# top.net
KiCad netlist of a schematic drawn in Altium Designer
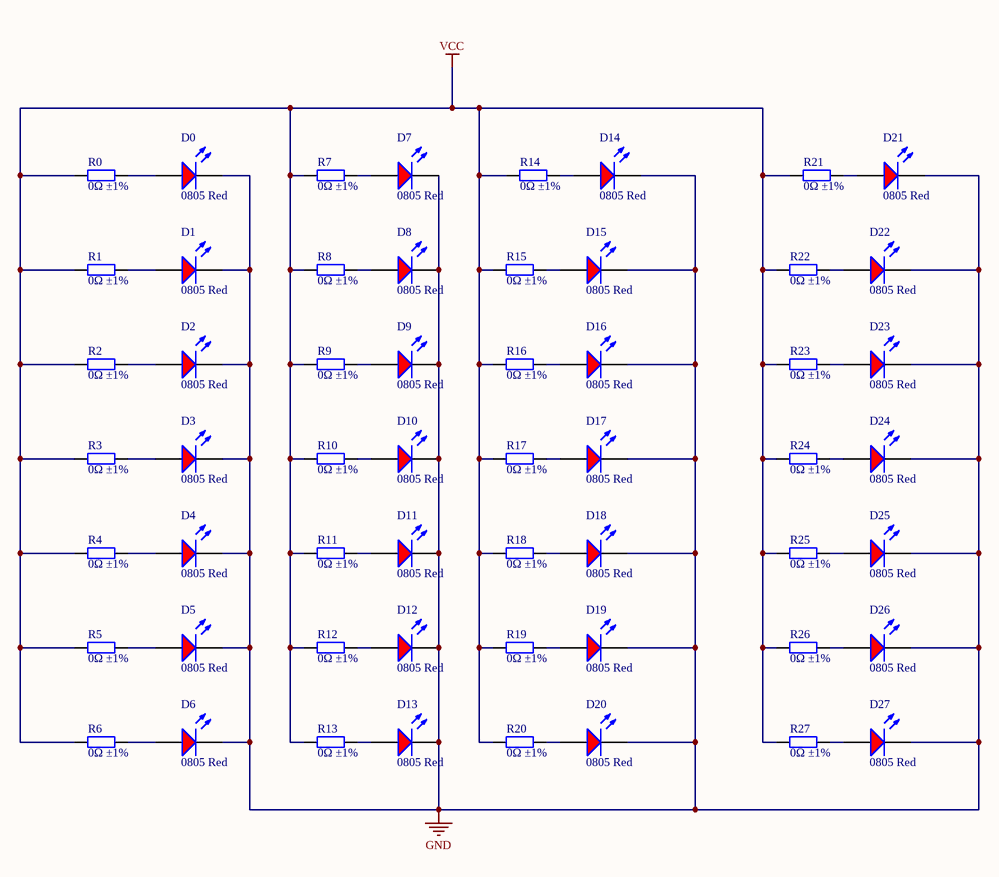
[diagram p0: top.SchDoc]

(export (version "E")
  (design (tool "Eeschema 10.0.6"))
  (components
    (comp (ref "D0")
      (value "0805 Red")
      (footprint "0805_LED_S1")
      (description "LED")
      (libsource (lib "Miscellaneous Devices LC") (part "0805 LED Red"))
    )
    (comp (ref "D1")
      (value "0805 Red")
      (footprint "0805_LED_S1")
      (description "LED")
      (libsource (lib "Miscellaneous Devices LC") (part "0805 LED Red"))
    )
    (comp (ref "D2")
      (value "0805 Red")
      (footprint "0805_LED_S1")
      (description "LED")
      (libsource (lib "Miscellaneous Devices LC") (part "0805 LED Red"))
    )
    (comp (ref "D3")
      (value "0805 Red")
      (footprint "0805_LED_S1")
      (description "LED")
      (libsource (lib "Miscellaneous Devices LC") (part "0805 LED Red"))
    )
    (comp (ref "D4")
      (value "0805 Red")
      (footprint "0805_LED_S1")
      (description "LED")
      (libsource (lib "Miscellaneous Devices LC") (part "0805 LED Red"))
    )
    (comp (ref "D5")
      (value "0805 Red")
      (footprint "0805_LED_S1")
      (description "LED")
      (libsource (lib "Miscellaneous Devices LC") (part "0805 LED Red"))
    )
    (comp (ref "D6")
      (value "0805 Red")
      (footprint "0805_LED_S1")
      (description "LED")
      (libsource (lib "Miscellaneous Devices LC") (part "0805 LED Red"))
    )
    (comp (ref "D7")
      (value "0805 Red")
      (footprint "0805_LED_S1")
      (description "LED")
      (libsource (lib "Miscellaneous Devices LC") (part "0805 LED Red"))
    )
    (comp (ref "D8")
      (value "0805 Red")
      (footprint "0805_LED_S1")
      (description "LED")
      (libsource (lib "Miscellaneous Devices LC") (part "0805 LED Red"))
    )
    (comp (ref "D9")
      (value "0805 Red")
      (footprint "0805_LED_S1")
      (description "LED")
      (libsource (lib "Miscellaneous Devices LC") (part "0805 LED Red"))
    )
    (comp (ref "D10")
      (value "0805 Red")
      (footprint "0805_LED_S1")
      (description "LED")
      (libsource (lib "Miscellaneous Devices LC") (part "0805 LED Red"))
    )
    (comp (ref "D11")
      (value "0805 Red")
      (footprint "0805_LED_S1")
      (description "LED")
      (libsource (lib "Miscellaneous Devices LC") (part "0805 LED Red"))
    )
    (comp (ref "D12")
      (value "0805 Red")
      (footprint "0805_LED_S1")
      (description "LED")
      (libsource (lib "Miscellaneous Devices LC") (part "0805 LED Red"))
    )
    (comp (ref "D13")
      (value "0805 Red")
      (footprint "0805_LED_S1")
      (description "LED")
      (libsource (lib "Miscellaneous Devices LC") (part "0805 LED Red"))
    )
    (comp (ref "D14")
      (value "0805 Red")
      (footprint "0805_LED_S1")
      (description "LED")
      (libsource (lib "Miscellaneous Devices LC") (part "0805 LED Red"))
    )
    (comp (ref "D15")
      (value "0805 Red")
      (footprint "0805_LED_S1")
      (description "LED")
      (libsource (lib "Miscellaneous Devices LC") (part "0805 LED Red"))
    )
    (comp (ref "D16")
      (value "0805 Red")
      (footprint "0805_LED_S1")
      (description "LED")
      (libsource (lib "Miscellaneous Devices LC") (part "0805 LED Red"))
    )
    (comp (ref "D17")
      (value "0805 Red")
      (footprint "0805_LED_S1")
      (description "LED")
      (libsource (lib "Miscellaneous Devices LC") (part "0805 LED Red"))
    )
    (comp (ref "D18")
      (value "0805 Red")
      (footprint "0805_LED_S1")
      (description "LED")
      (libsource (lib "Miscellaneous Devices LC") (part "0805 LED Red"))
    )
    (comp (ref "D19")
      (value "0805 Red")
      (footprint "0805_LED_S1")
      (description "LED")
      (libsource (lib "Miscellaneous Devices LC") (part "0805 LED Red"))
    )
    (comp (ref "D20")
      (value "0805 Red")
      (footprint "0805_LED_S1")
      (description "LED")
      (libsource (lib "Miscellaneous Devices LC") (part "0805 LED Red"))
    )
    (comp (ref "D21")
      (value "0805 Red")
      (footprint "0805_LED_S1")
      (description "LED")
      (libsource (lib "Miscellaneous Devices LC") (part "0805 LED Red"))
    )
    (comp (ref "D22")
      (value "0805 Red")
      (footprint "0805_LED_S1")
      (description "LED")
      (libsource (lib "Miscellaneous Devices LC") (part "0805 LED Red"))
    )
    (comp (ref "D23")
      (value "0805 Red")
      (footprint "0805_LED_S1")
      (description "LED")
      (libsource (lib "Miscellaneous Devices LC") (part "0805 LED Red"))
    )
    (comp (ref "D24")
      (value "0805 Red")
      (footprint "0805_LED_S1")
      (description "LED")
      (libsource (lib "Miscellaneous Devices LC") (part "0805 LED Red"))
    )
    (comp (ref "D25")
      (value "0805 Red")
      (footprint "0805_LED_S1")
      (description "LED")
      (libsource (lib "Miscellaneous Devices LC") (part "0805 LED Red"))
    )
    (comp (ref "D26")
      (value "0805 Red")
      (footprint "0805_LED_S1")
      (description "LED")
      (libsource (lib "Miscellaneous Devices LC") (part "0805 LED Red"))
    )
    (comp (ref "D27")
      (value "0805 Red")
      (footprint "0805_LED_S1")
      (description "LED")
      (libsource (lib "Miscellaneous Devices LC") (part "0805 LED Red"))
    )
    (comp (ref "R0")
      (value "0Ω ±1%")
      (footprint "0402_R")
      (description "Chip resistor")
      (fields (field (name "POWER") "1/16W") (field (name "MANUFACTURER") "Uniroyal Elec"))
      (libsource (lib "Miscellaneous Devices LC") (part "0402 0R (0R0) 1%"))
    )
    (comp (ref "R1")
      (value "0Ω ±1%")
      (footprint "0402_R")
      (description "Chip resistor")
      (fields (field (name "POWER") "1/16W") (field (name "MANUFACTURER") "Uniroyal Elec"))
      (libsource (lib "Miscellaneous Devices LC") (part "0402 0R (0R0) 1%"))
    )
    (comp (ref "R2")
      (value "0Ω ±1%")
      (footprint "0402_R")
      (description "Chip resistor")
      (fields (field (name "POWER") "1/16W") (field (name "MANUFACTURER") "Uniroyal Elec"))
      (libsource (lib "Miscellaneous Devices LC") (part "0402 0R (0R0) 1%"))
    )
    (comp (ref "R3")
      (value "0Ω ±1%")
      (footprint "0402_R")
      (description "Chip resistor")
      (fields (field (name "POWER") "1/16W") (field (name "MANUFACTURER") "Uniroyal Elec"))
      (libsource (lib "Miscellaneous Devices LC") (part "0402 0R (0R0) 1%"))
    )
    (comp (ref "R4")
      (value "0Ω ±1%")
      (footprint "0402_R")
      (description "Chip resistor")
      (fields (field (name "POWER") "1/16W") (field (name "MANUFACTURER") "Uniroyal Elec"))
      (libsource (lib "Miscellaneous Devices LC") (part "0402 0R (0R0) 1%"))
    )
    (comp (ref "R5")
      (value "0Ω ±1%")
      (footprint "0402_R")
      (description "Chip resistor")
      (fields (field (name "POWER") "1/16W") (field (name "MANUFACTURER") "Uniroyal Elec"))
      (libsource (lib "Miscellaneous Devices LC") (part "0402 0R (0R0) 1%"))
    )
    (comp (ref "R6")
      (value "0Ω ±1%")
      (footprint "0402_R")
      (description "Chip resistor")
      (fields (field (name "POWER") "1/16W") (field (name "MANUFACTURER") "Uniroyal Elec"))
      (libsource (lib "Miscellaneous Devices LC") (part "0402 0R (0R0) 1%"))
    )
    (comp (ref "R7")
      (value "0Ω ±1%")
      (footprint "0402_R")
      (description "Chip resistor")
      (fields (field (name "POWER") "1/16W") (field (name "MANUFACTURER") "Uniroyal Elec"))
      (libsource (lib "Miscellaneous Devices LC") (part "0402 0R (0R0) 1%"))
    )
    (comp (ref "R8")
      (value "0Ω ±1%")
      (footprint "0402_R")
      (description "Chip resistor")
      (fields (field (name "POWER") "1/16W") (field (name "MANUFACTURER") "Uniroyal Elec"))
      (libsource (lib "Miscellaneous Devices LC") (part "0402 0R (0R0) 1%"))
    )
    (comp (ref "R9")
      (value "0Ω ±1%")
      (footprint "0402_R")
      (description "Chip resistor")
      (fields (field (name "POWER") "1/16W") (field (name "MANUFACTURER") "Uniroyal Elec"))
      (libsource (lib "Miscellaneous Devices LC") (part "0402 0R (0R0) 1%"))
    )
    (comp (ref "R10")
      (value "0Ω ±1%")
      (footprint "0402_R")
      (description "Chip resistor")
      (fields (field (name "POWER") "1/16W") (field (name "MANUFACTURER") "Uniroyal Elec"))
      (libsource (lib "Miscellaneous Devices LC") (part "0402 0R (0R0) 1%"))
    )
    (comp (ref "R11")
      (value "0Ω ±1%")
      (footprint "0402_R")
      (description "Chip resistor")
      (fields (field (name "POWER") "1/16W") (field (name "MANUFACTURER") "Uniroyal Elec"))
      (libsource (lib "Miscellaneous Devices LC") (part "0402 0R (0R0) 1%"))
    )
    (comp (ref "R12")
      (value "0Ω ±1%")
      (footprint "0402_R")
      (description "Chip resistor")
      (fields (field (name "POWER") "1/16W") (field (name "MANUFACTURER") "Uniroyal Elec"))
      (libsource (lib "Miscellaneous Devices LC") (part "0402 0R (0R0) 1%"))
    )
    (comp (ref "R13")
      (value "0Ω ±1%")
      (footprint "0402_R")
      (description "Chip resistor")
      (fields (field (name "POWER") "1/16W") (field (name "MANUFACTURER") "Uniroyal Elec"))
      (libsource (lib "Miscellaneous Devices LC") (part "0402 0R (0R0) 1%"))
    )
    (comp (ref "R14")
      (value "0Ω ±1%")
      (footprint "0402_R")
      (description "Chip resistor")
      (fields (field (name "POWER") "1/16W") (field (name "MANUFACTURER") "Uniroyal Elec"))
      (libsource (lib "Miscellaneous Devices LC") (part "0402 0R (0R0) 1%"))
    )
    (comp (ref "R15")
      (value "0Ω ±1%")
      (footprint "0402_R")
      (description "Chip resistor")
      (fields (field (name "POWER") "1/16W") (field (name "MANUFACTURER") "Uniroyal Elec"))
      (libsource (lib "Miscellaneous Devices LC") (part "0402 0R (0R0) 1%"))
    )
    (comp (ref "R16")
      (value "0Ω ±1%")
      (footprint "0402_R")
      (description "Chip resistor")
      (fields (field (name "POWER") "1/16W") (field (name "MANUFACTURER") "Uniroyal Elec"))
      (libsource (lib "Miscellaneous Devices LC") (part "0402 0R (0R0) 1%"))
    )
    (comp (ref "R17")
      (value "0Ω ±1%")
      (footprint "0402_R")
      (description "Chip resistor")
      (fields (field (name "POWER") "1/16W") (field (name "MANUFACTURER") "Uniroyal Elec"))
      (libsource (lib "Miscellaneous Devices LC") (part "0402 0R (0R0) 1%"))
    )
    (comp (ref "R18")
      (value "0Ω ±1%")
      (footprint "0402_R")
      (description "Chip resistor")
      (fields (field (name "POWER") "1/16W") (field (name "MANUFACTURER") "Uniroyal Elec"))
      (libsource (lib "Miscellaneous Devices LC") (part "0402 0R (0R0) 1%"))
    )
    (comp (ref "R19")
      (value "0Ω ±1%")
      (footprint "0402_R")
      (description "Chip resistor")
      (fields (field (name "POWER") "1/16W") (field (name "MANUFACTURER") "Uniroyal Elec"))
      (libsource (lib "Miscellaneous Devices LC") (part "0402 0R (0R0) 1%"))
    )
    (comp (ref "R20")
      (value "0Ω ±1%")
      (footprint "0402_R")
      (description "Chip resistor")
      (fields (field (name "POWER") "1/16W") (field (name "MANUFACTURER") "Uniroyal Elec"))
      (libsource (lib "Miscellaneous Devices LC") (part "0402 0R (0R0) 1%"))
    )
    (comp (ref "R21")
      (value "0Ω ±1%")
      (footprint "0402_R")
      (description "Chip resistor")
      (fields (field (name "POWER") "1/16W") (field (name "MANUFACTURER") "Uniroyal Elec"))
      (libsource (lib "Miscellaneous Devices LC") (part "0402 0R (0R0) 1%"))
    )
    (comp (ref "R22")
      (value "0Ω ±1%")
      (footprint "0402_R")
      (description "Chip resistor")
      (fields (field (name "POWER") "1/16W") (field (name "MANUFACTURER") "Uniroyal Elec"))
      (libsource (lib "Miscellaneous Devices LC") (part "0402 0R (0R0) 1%"))
    )
    (comp (ref "R23")
      (value "0Ω ±1%")
      (footprint "0402_R")
      (description "Chip resistor")
      (fields (field (name "POWER") "1/16W") (field (name "MANUFACTURER") "Uniroyal Elec"))
      (libsource (lib "Miscellaneous Devices LC") (part "0402 0R (0R0) 1%"))
    )
    (comp (ref "R24")
      (value "0Ω ±1%")
      (footprint "0402_R")
      (description "Chip resistor")
      (fields (field (name "POWER") "1/16W") (field (name "MANUFACTURER") "Uniroyal Elec"))
      (libsource (lib "Miscellaneous Devices LC") (part "0402 0R (0R0) 1%"))
    )
    (comp (ref "R25")
      (value "0Ω ±1%")
      (footprint "0402_R")
      (description "Chip resistor")
      (fields (field (name "POWER") "1/16W") (field (name "MANUFACTURER") "Uniroyal Elec"))
      (libsource (lib "Miscellaneous Devices LC") (part "0402 0R (0R0) 1%"))
    )
    (comp (ref "R26")
      (value "0Ω ±1%")
      (footprint "0402_R")
      (description "Chip resistor")
      (fields (field (name "POWER") "1/16W") (field (name "MANUFACTURER") "Uniroyal Elec"))
      (libsource (lib "Miscellaneous Devices LC") (part "0402 0R (0R0) 1%"))
    )
    (comp (ref "R27")
      (value "0Ω ±1%")
      (footprint "0402_R")
      (description "Chip resistor")
      (fields (field (name "POWER") "1/16W") (field (name "MANUFACTURER") "Uniroyal Elec"))
      (libsource (lib "Miscellaneous Devices LC") (part "0402 0R (0R0) 1%"))
    )
  )
  (nets
    (net (code "1") (name "GND") (class "Default")
      (node (ref "D0") (pin "K") (pinfunction "K_K") (pintype "passive"))
      (node (ref "D1") (pin "K") (pinfunction "K_K") (pintype "passive"))
      (node (ref "D10") (pin "K") (pinfunction "K_K") (pintype "passive"))
      (node (ref "D11") (pin "K") (pinfunction "K_K") (pintype "passive"))
      (node (ref "D12") (pin "K") (pinfunction "K_K") (pintype "passive"))
      (node (ref "D13") (pin "K") (pinfunction "K_K") (pintype "passive"))
      (node (ref "D14") (pin "K") (pinfunction "K_K") (pintype "passive"))
      (node (ref "D15") (pin "K") (pinfunction "K_K") (pintype "passive"))
      (node (ref "D16") (pin "K") (pinfunction "K_K") (pintype "passive"))
      (node (ref "D17") (pin "K") (pinfunction "K_K") (pintype "passive"))
      (node (ref "D18") (pin "K") (pinfunction "K_K") (pintype "passive"))
      (node (ref "D19") (pin "K") (pinfunction "K_K") (pintype "passive"))
      (node (ref "D2") (pin "K") (pinfunction "K_K") (pintype "passive"))
      (node (ref "D20") (pin "K") (pinfunction "K_K") (pintype "passive"))
      (node (ref "D21") (pin "K") (pinfunction "K_K") (pintype "passive"))
      (node (ref "D22") (pin "K") (pinfunction "K_K") (pintype "passive"))
      (node (ref "D23") (pin "K") (pinfunction "K_K") (pintype "passive"))
      (node (ref "D24") (pin "K") (pinfunction "K_K") (pintype "passive"))
      (node (ref "D25") (pin "K") (pinfunction "K_K") (pintype "passive"))
      (node (ref "D26") (pin "K") (pinfunction "K_K") (pintype "passive"))
      (node (ref "D27") (pin "K") (pinfunction "K_K") (pintype "passive"))
      (node (ref "D3") (pin "K") (pinfunction "K_K") (pintype "passive"))
      (node (ref "D4") (pin "K") (pinfunction "K_K") (pintype "passive"))
      (node (ref "D5") (pin "K") (pinfunction "K_K") (pintype "passive"))
      (node (ref "D6") (pin "K") (pinfunction "K_K") (pintype "passive"))
      (node (ref "D7") (pin "K") (pinfunction "K_K") (pintype "passive"))
      (node (ref "D8") (pin "K") (pinfunction "K_K") (pintype "passive"))
      (node (ref "D9") (pin "K") (pinfunction "K_K") (pintype "passive"))
    )
    (net (code "2") (name "Net-(D0-PadA)") (class "Default")
      (node (ref "D0") (pin "A") (pinfunction "A_A") (pintype "passive"))
      (node (ref "R0") (pin "2") (pinfunction "2_2") (pintype "passive"))
    )
    (net (code "3") (name "Net-(D1-PadA)") (class "Default")
      (node (ref "D1") (pin "A") (pinfunction "A_A") (pintype "passive"))
      (node (ref "R1") (pin "2") (pinfunction "2_2") (pintype "passive"))
    )
    (net (code "4") (name "Net-(D2-PadA)") (class "Default")
      (node (ref "D2") (pin "A") (pinfunction "A_A") (pintype "passive"))
      (node (ref "R2") (pin "2") (pinfunction "2_2") (pintype "passive"))
    )
    (net (code "5") (name "Net-(D3-PadA)") (class "Default")
      (node (ref "D3") (pin "A") (pinfunction "A_A") (pintype "passive"))
      (node (ref "R3") (pin "2") (pinfunction "2_2") (pintype "passive"))
    )
    (net (code "6") (name "Net-(D4-PadA)") (class "Default")
      (node (ref "D4") (pin "A") (pinfunction "A_A") (pintype "passive"))
      (node (ref "R4") (pin "2") (pinfunction "2_2") (pintype "passive"))
    )
    (net (code "7") (name "Net-(D5-PadA)") (class "Default")
      (node (ref "D5") (pin "A") (pinfunction "A_A") (pintype "passive"))
      (node (ref "R5") (pin "2") (pinfunction "2_2") (pintype "passive"))
    )
    (net (code "8") (name "Net-(D6-PadA)") (class "Default")
      (node (ref "D6") (pin "A") (pinfunction "A_A") (pintype "passive"))
      (node (ref "R6") (pin "2") (pinfunction "2_2") (pintype "passive"))
    )
    (net (code "9") (name "Net-(D7-PadA)") (class "Default")
      (node (ref "D7") (pin "A") (pinfunction "A_A") (pintype "passive"))
      (node (ref "R7") (pin "2") (pinfunction "2_2") (pintype "passive"))
    )
    (net (code "10") (name "Net-(D8-PadA)") (class "Default")
      (node (ref "D8") (pin "A") (pinfunction "A_A") (pintype "passive"))
      (node (ref "R8") (pin "2") (pinfunction "2_2") (pintype "passive"))
    )
    (net (code "11") (name "Net-(D9-PadA)") (class "Default")
      (node (ref "D9") (pin "A") (pinfunction "A_A") (pintype "passive"))
      (node (ref "R9") (pin "2") (pinfunction "2_2") (pintype "passive"))
    )
    (net (code "12") (name "Net-(D10-PadA)") (class "Default")
      (node (ref "D10") (pin "A") (pinfunction "A_A") (pintype "passive"))
      (node (ref "R10") (pin "2") (pinfunction "2_2") (pintype "passive"))
    )
    (net (code "13") (name "Net-(D11-PadA)") (class "Default")
      (node (ref "D11") (pin "A") (pinfunction "A_A") (pintype "passive"))
      (node (ref "R11") (pin "2") (pinfunction "2_2") (pintype "passive"))
    )
    (net (code "14") (name "Net-(D12-PadA)") (class "Default")
      (node (ref "D12") (pin "A") (pinfunction "A_A") (pintype "passive"))
      (node (ref "R12") (pin "2") (pinfunction "2_2") (pintype "passive"))
    )
    (net (code "15") (name "Net-(D13-PadA)") (class "Default")
      (node (ref "D13") (pin "A") (pinfunction "A_A") (pintype "passive"))
      (node (ref "R13") (pin "2") (pinfunction "2_2") (pintype "passive"))
    )
    (net (code "16") (name "Net-(D14-PadA)") (class "Default")
      (node (ref "D14") (pin "A") (pinfunction "A_A") (pintype "passive"))
      (node (ref "R14") (pin "2") (pinfunction "2_2") (pintype "passive"))
    )
    (net (code "17") (name "Net-(D15-PadA)") (class "Default")
      (node (ref "D15") (pin "A") (pinfunction "A_A") (pintype "passive"))
      (node (ref "R15") (pin "2") (pinfunction "2_2") (pintype "passive"))
    )
    (net (code "18") (name "Net-(D16-PadA)") (class "Default")
      (node (ref "D16") (pin "A") (pinfunction "A_A") (pintype "passive"))
      (node (ref "R16") (pin "2") (pinfunction "2_2") (pintype "passive"))
    )
    (net (code "19") (name "Net-(D17-PadA)") (class "Default")
      (node (ref "D17") (pin "A") (pinfunction "A_A") (pintype "passive"))
      (node (ref "R17") (pin "2") (pinfunction "2_2") (pintype "passive"))
    )
    (net (code "20") (name "Net-(D18-PadA)") (class "Default")
      (node (ref "D18") (pin "A") (pinfunction "A_A") (pintype "passive"))
      (node (ref "R18") (pin "2") (pinfunction "2_2") (pintype "passive"))
    )
    (net (code "21") (name "Net-(D19-PadA)") (class "Default")
      (node (ref "D19") (pin "A") (pinfunction "A_A") (pintype "passive"))
      (node (ref "R19") (pin "2") (pinfunction "2_2") (pintype "passive"))
    )
    (net (code "22") (name "Net-(D20-PadA)") (class "Default")
      (node (ref "D20") (pin "A") (pinfunction "A_A") (pintype "passive"))
      (node (ref "R20") (pin "2") (pinfunction "2_2") (pintype "passive"))
    )
    (net (code "23") (name "Net-(D21-PadA)") (class "Default")
      (node (ref "D21") (pin "A") (pinfunction "A_A") (pintype "passive"))
      (node (ref "R21") (pin "2") (pinfunction "2_2") (pintype "passive"))
    )
    (net (code "24") (name "Net-(D22-PadA)") (class "Default")
      (node (ref "D22") (pin "A") (pinfunction "A_A") (pintype "passive"))
      (node (ref "R22") (pin "2") (pinfunction "2_2") (pintype "passive"))
    )
    (net (code "25") (name "Net-(D23-PadA)") (class "Default")
      (node (ref "D23") (pin "A") (pinfunction "A_A") (pintype "passive"))
      (node (ref "R23") (pin "2") (pinfunction "2_2") (pintype "passive"))
    )
    (net (code "26") (name "Net-(D24-PadA)") (class "Default")
      (node (ref "D24") (pin "A") (pinfunction "A_A") (pintype "passive"))
      (node (ref "R24") (pin "2") (pinfunction "2_2") (pintype "passive"))
    )
    (net (code "27") (name "Net-(D25-PadA)") (class "Default")
      (node (ref "D25") (pin "A") (pinfunction "A_A") (pintype "passive"))
      (node (ref "R25") (pin "2") (pinfunction "2_2") (pintype "passive"))
    )
    (net (code "28") (name "Net-(D26-PadA)") (class "Default")
      (node (ref "D26") (pin "A") (pinfunction "A_A") (pintype "passive"))
      (node (ref "R26") (pin "2") (pinfunction "2_2") (pintype "passive"))
    )
    (net (code "29") (name "Net-(D27-PadA)") (class "Default")
      (node (ref "D27") (pin "A") (pinfunction "A_A") (pintype "passive"))
      (node (ref "R27") (pin "2") (pinfunction "2_2") (pintype "passive"))
    )
    (net (code "30") (name "VCC") (class "Default")
      (node (ref "R0") (pin "1") (pinfunction "1_1") (pintype "passive"))
      (node (ref "R1") (pin "1") (pinfunction "1_1") (pintype "passive"))
      (node (ref "R10") (pin "1") (pinfunction "1_1") (pintype "passive"))
      (node (ref "R11") (pin "1") (pinfunction "1_1") (pintype "passive"))
      (node (ref "R12") (pin "1") (pinfunction "1_1") (pintype "passive"))
      (node (ref "R13") (pin "1") (pinfunction "1_1") (pintype "passive"))
      (node (ref "R14") (pin "1") (pinfunction "1_1") (pintype "passive"))
      (node (ref "R15") (pin "1") (pinfunction "1_1") (pintype "passive"))
      (node (ref "R16") (pin "1") (pinfunction "1_1") (pintype "passive"))
      (node (ref "R17") (pin "1") (pinfunction "1_1") (pintype "passive"))
      (node (ref "R18") (pin "1") (pinfunction "1_1") (pintype "passive"))
      (node (ref "R19") (pin "1") (pinfunction "1_1") (pintype "passive"))
      (node (ref "R2") (pin "1") (pinfunction "1_1") (pintype "passive"))
      (node (ref "R20") (pin "1") (pinfunction "1_1") (pintype "passive"))
      (node (ref "R21") (pin "1") (pinfunction "1_1") (pintype "passive"))
      (node (ref "R22") (pin "1") (pinfunction "1_1") (pintype "passive"))
      (node (ref "R23") (pin "1") (pinfunction "1_1") (pintype "passive"))
      (node (ref "R24") (pin "1") (pinfunction "1_1") (pintype "passive"))
      (node (ref "R25") (pin "1") (pinfunction "1_1") (pintype "passive"))
      (node (ref "R26") (pin "1") (pinfunction "1_1") (pintype "passive"))
      (node (ref "R27") (pin "1") (pinfunction "1_1") (pintype "passive"))
      (node (ref "R3") (pin "1") (pinfunction "1_1") (pintype "passive"))
      (node (ref "R4") (pin "1") (pinfunction "1_1") (pintype "passive"))
      (node (ref "R5") (pin "1") (pinfunction "1_1") (pintype "passive"))
      (node (ref "R6") (pin "1") (pinfunction "1_1") (pintype "passive"))
      (node (ref "R7") (pin "1") (pinfunction "1_1") (pintype "passive"))
      (node (ref "R8") (pin "1") (pinfunction "1_1") (pintype "passive"))
      (node (ref "R9") (pin "1") (pinfunction "1_1") (pintype "passive"))
    )
  )
)
